# FPGA_Misc.net
KiCad netlist of a schematic drawn in Altium Designer
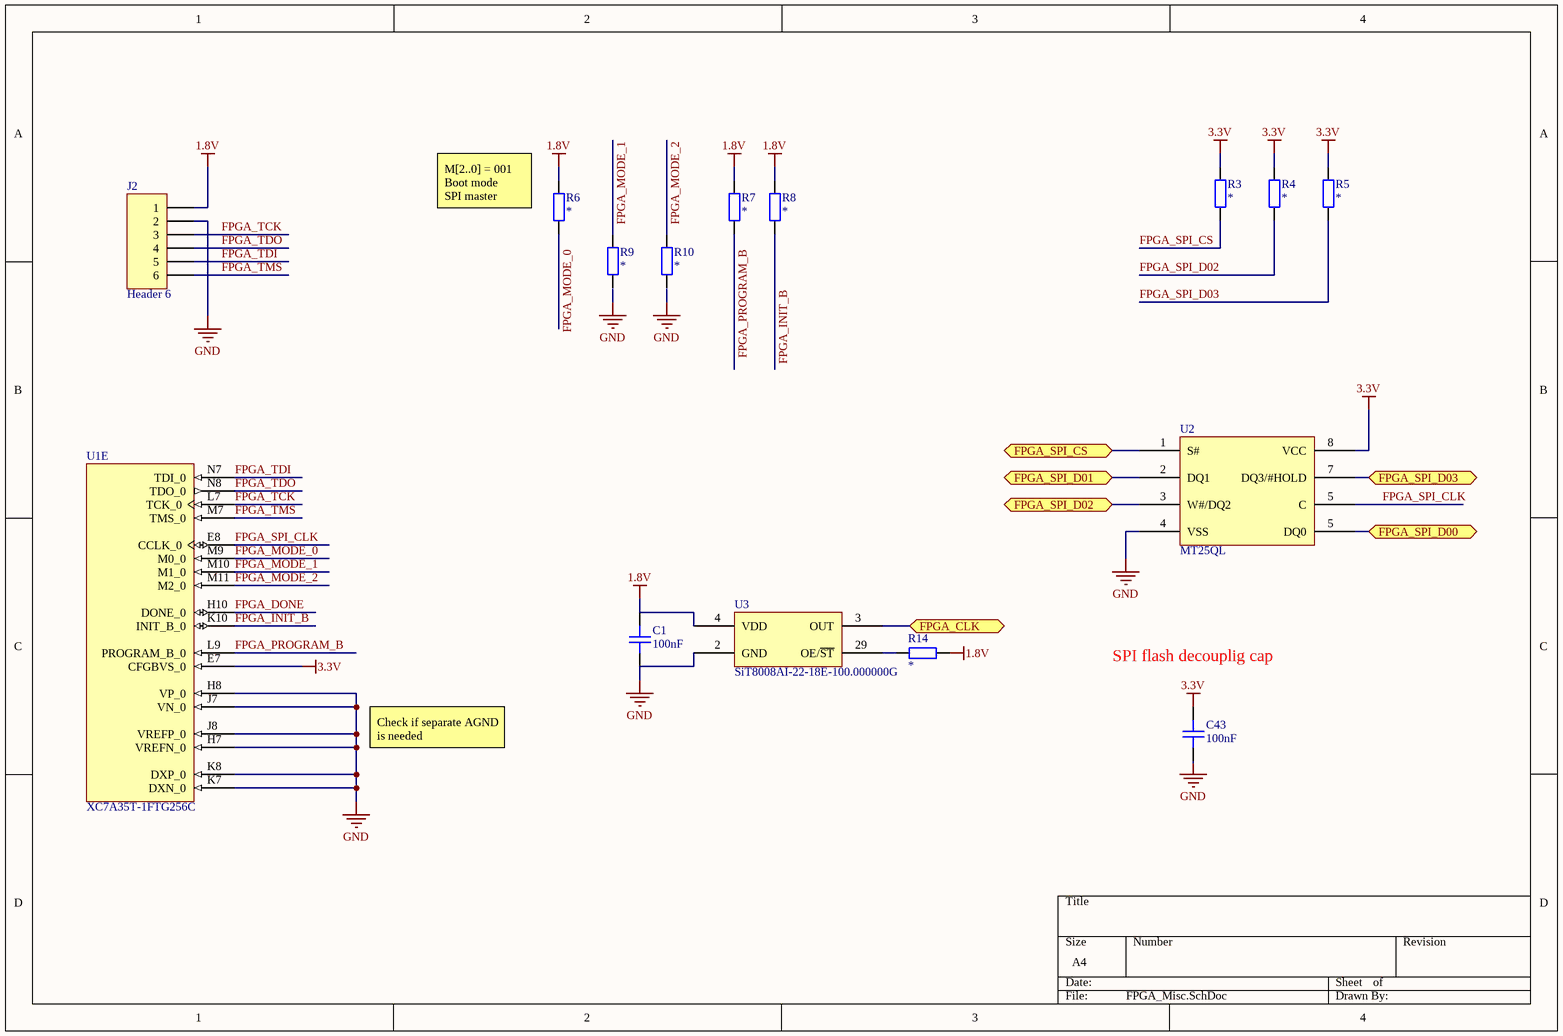
[diagram p0: FPGA_Misc.SchDoc]

(export (version "E")
  (design (tool "Eeschema 10.0.6"))
  (components
    (comp (ref "C1") (value "100nF") (footprint "CAP0402") (libsource (lib "WaveRadio") (part "Cap_0402")))
    (comp (ref "C43") (value "100nF") (footprint "CAP0402") (libsource (lib "WaveRadio") (part "Cap_0402")))
    (comp (ref "J2")
      (value "Header 6")
      (footprint "HDR1X6")
      (description "Header, 6-Pin")
      (fields (field (name "PUBLISHER") "Altium Limited"))
      (libsource (lib "Miscellaneous Connectors") (part "Header 6"))
    )
    (comp (ref "R3") (value "*") (footprint "RES0402") (libsource (lib "WaveRadio") (part "Res_0402")))
    (comp (ref "R4") (value "*") (footprint "RES0402") (libsource (lib "WaveRadio") (part "Res_0402")))
    (comp (ref "R5") (value "*") (footprint "RES0402") (libsource (lib "WaveRadio") (part "Res_0402")))
    (comp (ref "R6") (value "*") (footprint "RES0402") (libsource (lib "WaveRadio") (part "Res_0402")))
    (comp (ref "R7") (value "*") (footprint "RES0402") (libsource (lib "WaveRadio") (part "Res_0402")))
    (comp (ref "R8") (value "*") (footprint "RES0402") (libsource (lib "WaveRadio") (part "Res_0402")))
    (comp (ref "R9") (value "*") (footprint "RES0402") (libsource (lib "WaveRadio") (part "Res_0402")))
    (comp (ref "R10") (value "*") (footprint "RES0402") (libsource (lib "WaveRadio") (part "Res_0402")))
    (comp (ref "R14") (value "*") (footprint "RES0402") (libsource (lib "WaveRadio") (part "Res_0402")))
    (comp (ref "U1")
      (value "XC7A35T-1FTG256C")
      (footprint "FTG256")
      (description "Artix-7 FPGA, 170 User I/Os, 0 GTP, 256-Ball BGA, Speed Grade 1, Commercial Grade, Pb-Free")
      (fields (field (name "MANUFACTURER") "Xilinx"))
      (libsource (lib "Xilinx Artix-7") (part "XC7A35T-1FTG256C"))
    )
    (comp (ref "U2") (value "MT25QL") (libsource (lib "WaveRadio") (part "MT25QL")))
    (comp (ref "U3")
      (value "SiT8008AI-22-18E-100.000000G")
      (libsource (lib "WaveRadio") (part "SiT8008AI-22-18E-100.000000G"))
    )
  )
  (nets
    (net (code "1") (name "/FPGA_CLK") (class "Default")
      (node (ref "U3") (pin "3") (pinfunction "OUT_3") (pintype "passive"))
    )
    (net (code "2") (name "/FPGA_DONE") (class "Default")
      (node (ref "U1") (pin "H10") (pinfunction "DONE_0_H10") (pintype "bidirectional"))
    )
    (net (code "3") (name "/FPGA_INIT_B") (class "Default")
      (node (ref "U1") (pin "K10") (pinfunction "INIT_B_0_K10") (pintype "bidirectional"))
    )
    (net (code "4") (name "/FPGA_MODE_0") (class "Default")
      (node (ref "U1") (pin "M9") (pinfunction "M0_0_M9") (pintype "input"))
    )
    (net (code "5") (name "/FPGA_MODE_1") (class "Default")
      (node (ref "U1") (pin "M10") (pinfunction "M1_0_M10") (pintype "input"))
    )
    (net (code "6") (name "/FPGA_MODE_2") (class "Default")
      (node (ref "U1") (pin "M11") (pinfunction "M2_0_M11") (pintype "input"))
    )
    (net (code "7") (name "/FPGA_PROGRAM_B") (class "Default")
      (node (ref "U1") (pin "L9") (pinfunction "PROGRAM_B_0_L9") (pintype "input"))
    )
    (net (code "8") (name "/FPGA_SPI_CLK") (class "Default")
      (node (ref "U1") (pin "E8") (pinfunction "CCLK_0_E8") (pintype "bidirectional"))
      (node (ref "U2") (pin "5") (pinfunction "C_5") (pintype "passive"))
    )
    (net (code "9") (name "/FPGA_SPI_CS") (class "Default")
      (node (ref "U2") (pin "1") (pinfunction "S#_1") (pintype "passive"))
    )
    (net (code "10") (name "/FPGA_SPI_D00") (class "Default")
      (node (ref "U2") (pin "5") (pinfunction "DQ0_5") (pintype "passive"))
    )
    (net (code "11") (name "/FPGA_SPI_D01") (class "Default")
      (node (ref "U2") (pin "2") (pinfunction "DQ1_2") (pintype "passive"))
    )
    (net (code "12") (name "/FPGA_SPI_D02") (class "Default")
      (node (ref "U2") (pin "3") (pinfunction "W#/DQ2_3") (pintype "passive"))
    )
    (net (code "13") (name "/FPGA_SPI_D03") (class "Default")
      (node (ref "U2") (pin "7") (pinfunction "DQ3/#HOLD_7") (pintype "passive"))
    )
    (net (code "14") (name "/FPGA_TCK") (class "Default")
      (node (ref "J2") (pin "3") (pinfunction "3_3") (pintype "passive"))
      (node (ref "U1") (pin "L7") (pinfunction "TCK_0_L7") (pintype "input"))
    )
    (net (code "15") (name "/FPGA_TDI") (class "Default")
      (node (ref "J2") (pin "5") (pinfunction "5_5") (pintype "passive"))
      (node (ref "U1") (pin "N7") (pinfunction "TDI_0_N7") (pintype "input"))
    )
    (net (code "16") (name "/FPGA_TDO") (class "Default")
      (node (ref "J2") (pin "4") (pinfunction "4_4") (pintype "passive"))
      (node (ref "U1") (pin "N8") (pinfunction "TDO_0_N8") (pintype "output"))
    )
    (net (code "17") (name "/FPGA_TMS") (class "Default")
      (node (ref "J2") (pin "6") (pinfunction "6_6") (pintype "passive"))
      (node (ref "U1") (pin "M7") (pinfunction "TMS_0_M7") (pintype "input"))
    )
    (net (code "18") (name "1.8V") (class "Default")
      (node (ref "J2") (pin "1") (pinfunction "1_1") (pintype "passive"))
      (node (ref "U3") (pin "4") (pinfunction "VDD_4") (pintype "passive"))
    )
    (net (code "19") (name "3.3V") (class "Default")
      (node (ref "U1") (pin "E7") (pinfunction "CFGBVS_0_E7") (pintype "input"))
      (node (ref "U2") (pin "8") (pinfunction "VCC_8") (pintype "passive"))
    )
    (net (code "20") (name "GND") (class "Default")
      (node (ref "J2") (pin "2") (pinfunction "2_2") (pintype "passive"))
      (node (ref "U1") (pin "H7") (pinfunction "VREFN_0_H7") (pintype "input"))
      (node (ref "U1") (pin "H8") (pinfunction "VP_0_H8") (pintype "input"))
      (node (ref "U1") (pin "J7") (pinfunction "VN_0_J7") (pintype "input"))
      (node (ref "U1") (pin "J8") (pinfunction "VREFP_0_J8") (pintype "input"))
      (node (ref "U1") (pin "K7") (pinfunction "DXN_0_K7") (pintype "input"))
      (node (ref "U1") (pin "K8") (pinfunction "DXP_0_K8") (pintype "input"))
      (node (ref "U2") (pin "4") (pinfunction "VSS_4") (pintype "passive"))
      (node (ref "U3") (pin "2") (pinfunction "GND_2") (pintype "passive"))
    )
    (net (code "21") (name "unconnected-(C1-Pad1)") (class "Default")
      (node (ref "C1") (pin "1") (pinfunction "1_1") (pintype "passive"))
    )
    (net (code "22") (name "unconnected-(C1-Pad2)") (class "Default")
      (node (ref "C1") (pin "2") (pinfunction "2_2") (pintype "passive"))
    )
    (net (code "23") (name "unconnected-(C43-Pad1)") (class "Default")
      (node (ref "C43") (pin "1") (pinfunction "1_1") (pintype "passive"))
    )
    (net (code "24") (name "unconnected-(C43-Pad2)") (class "Default")
      (node (ref "C43") (pin "2") (pinfunction "2_2") (pintype "passive"))
    )
    (net (code "25") (name "unconnected-(R3-Pad1)") (class "Default")
      (node (ref "R3") (pin "1") (pintype "passive"))
    )
    (net (code "26") (name "unconnected-(R3-Pad2)") (class "Default")
      (node (ref "R3") (pin "2") (pintype "passive"))
    )
    (net (code "27") (name "unconnected-(R4-Pad1)") (class "Default")
      (node (ref "R4") (pin "1") (pintype "passive"))
    )
    (net (code "28") (name "unconnected-(R4-Pad2)") (class "Default")
      (node (ref "R4") (pin "2") (pintype "passive"))
    )
    (net (code "29") (name "unconnected-(R5-Pad1)") (class "Default")
      (node (ref "R5") (pin "1") (pintype "passive"))
    )
    (net (code "30") (name "unconnected-(R5-Pad2)") (class "Default")
      (node (ref "R5") (pin "2") (pintype "passive"))
    )
    (net (code "31") (name "unconnected-(R6-Pad1)") (class "Default")
      (node (ref "R6") (pin "1") (pintype "passive"))
    )
    (net (code "32") (name "unconnected-(R6-Pad2)") (class "Default")
      (node (ref "R6") (pin "2") (pintype "passive"))
    )
    (net (code "33") (name "unconnected-(R7-Pad1)") (class "Default")
      (node (ref "R7") (pin "1") (pintype "passive"))
    )
    (net (code "34") (name "unconnected-(R7-Pad2)") (class "Default")
      (node (ref "R7") (pin "2") (pintype "passive"))
    )
    (net (code "35") (name "unconnected-(R8-Pad1)") (class "Default")
      (node (ref "R8") (pin "1") (pintype "passive"))
    )
    (net (code "36") (name "unconnected-(R8-Pad2)") (class "Default")
      (node (ref "R8") (pin "2") (pintype "passive"))
    )
    (net (code "37") (name "unconnected-(R9-Pad1)") (class "Default")
      (node (ref "R9") (pin "1") (pintype "passive"))
    )
    (net (code "38") (name "unconnected-(R9-Pad2)") (class "Default")
      (node (ref "R9") (pin "2") (pintype "passive"))
    )
    (net (code "39") (name "unconnected-(R10-Pad1)") (class "Default")
      (node (ref "R10") (pin "1") (pintype "passive"))
    )
    (net (code "40") (name "unconnected-(R10-Pad2)") (class "Default")
      (node (ref "R10") (pin "2") (pintype "passive"))
    )
    (net (code "41") (name "unconnected-(R14-Pad1)") (class "Default")
      (node (ref "R14") (pin "1") (pintype "passive"))
    )
    (net (code "42") (name "unconnected-(R14-Pad2)") (class "Default")
      (node (ref "R14") (pin "2") (pintype "passive"))
    )
    (net (code "43") (name "unconnected-(U3-OE{slash}~{ST}-Pad29)") (class "Default")
      (node (ref "U3") (pin "29") (pinfunction "OE/~{ST}_29") (pintype "passive"))
    )
  )
)
